# BaseBoard_2x5.net
KiCad netlist of a schematic drawn in EAGLE
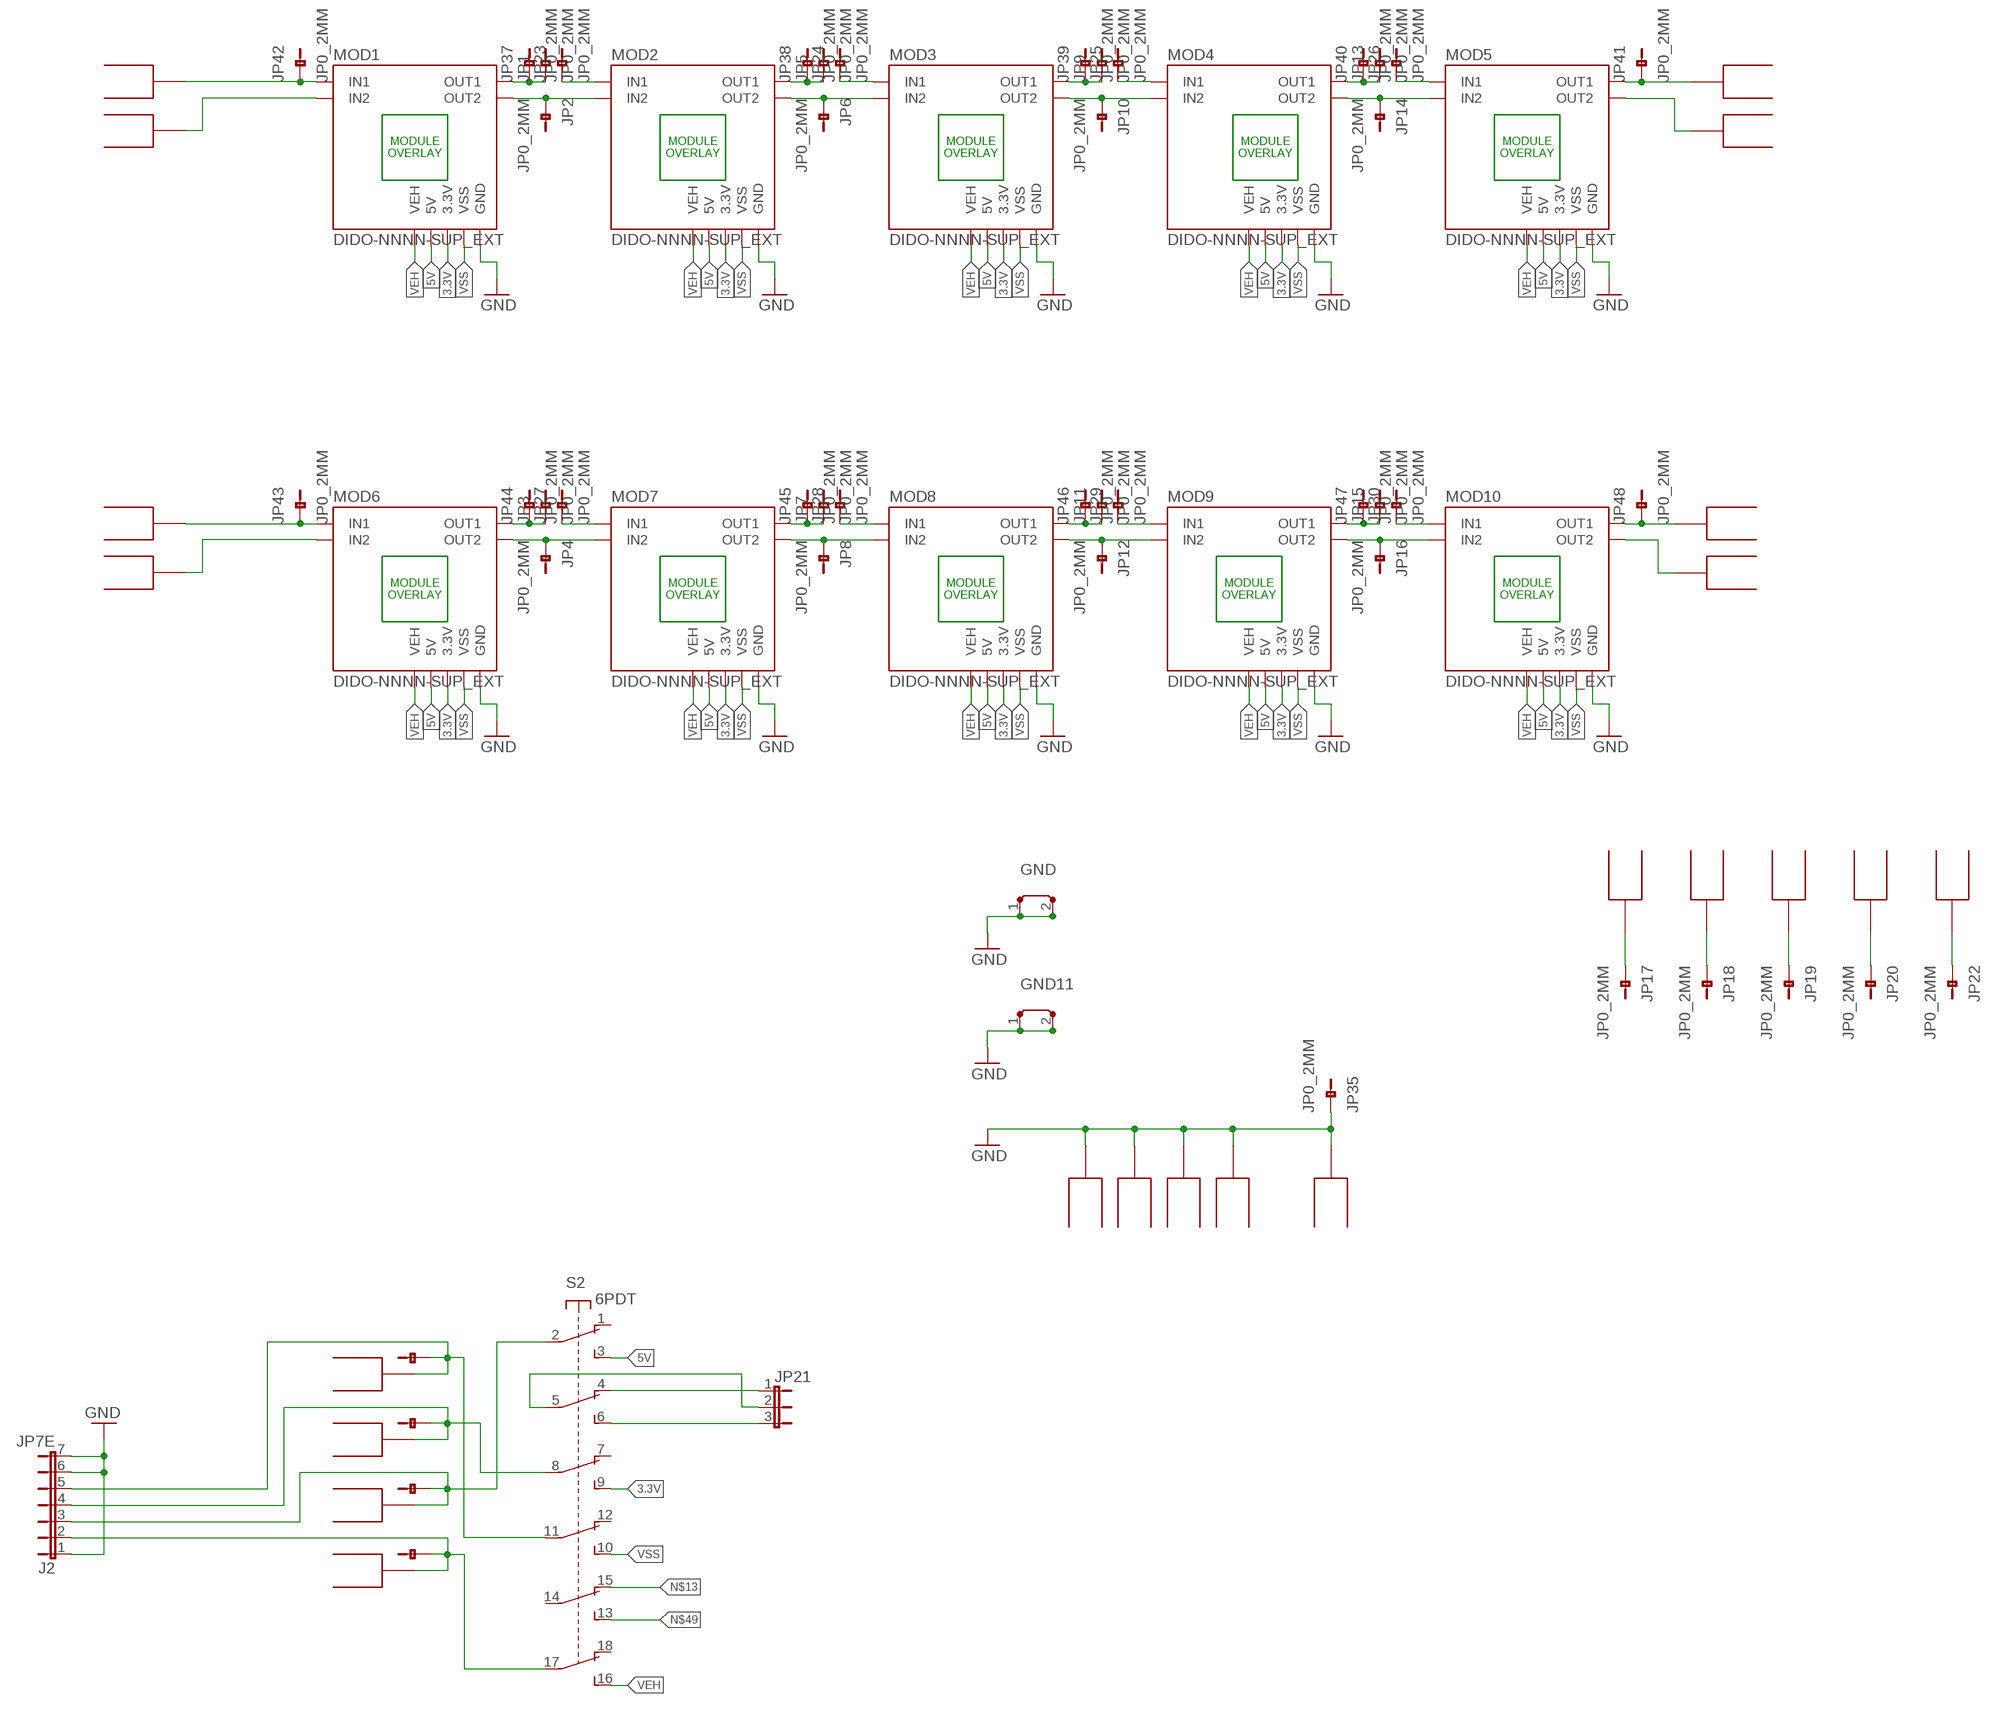
[diagram p0: schematic, sheet 1]

(export (version "E")
  (design (tool "Eeschema 10.0.6"))
  (components
    (comp (ref "GND")
      (value "TE4/2")
      (footprint "eagle-import:TE4_2")
      (libsource (lib "eagle-import") (part "TE4/2"))
    )
    (comp (ref "GND11")
      (value "TE4/2")
      (footprint "eagle-import:TE4_2")
      (libsource (lib "eagle-import") (part "TE4/2"))
    )
    (comp (ref "J2")
      (value "JP7E")
      (footprint "eagle-import:JP7")
      (libsource (lib "eagle-import") (part "JP7E"))
    )
    (comp (ref "JP1")
      (value "JP0_2MM")
      (footprint "eagle-import:JP0-2MM")
      (libsource (lib "eagle-import") (part "JP0_2MM"))
    )
    (comp (ref "JP2")
      (value "JP0_2MM")
      (footprint "eagle-import:JP0-2MM")
      (libsource (lib "eagle-import") (part "JP0_2MM"))
    )
    (comp (ref "JP3")
      (value "JP0_2MM")
      (footprint "eagle-import:JP0-2MM")
      (libsource (lib "eagle-import") (part "JP0_2MM"))
    )
    (comp (ref "JP4")
      (value "JP0_2MM")
      (footprint "eagle-import:JP0-2MM")
      (libsource (lib "eagle-import") (part "JP0_2MM"))
    )
    (comp (ref "JP5")
      (value "JP0_2MM")
      (footprint "eagle-import:JP0-2MM")
      (libsource (lib "eagle-import") (part "JP0_2MM"))
    )
    (comp (ref "JP6")
      (value "JP0_2MM")
      (footprint "eagle-import:JP0-2MM")
      (libsource (lib "eagle-import") (part "JP0_2MM"))
    )
    (comp (ref "JP7")
      (value "JP0_2MM")
      (footprint "eagle-import:JP0-2MM")
      (libsource (lib "eagle-import") (part "JP0_2MM"))
    )
    (comp (ref "JP8")
      (value "JP0_2MM")
      (footprint "eagle-import:JP0-2MM")
      (libsource (lib "eagle-import") (part "JP0_2MM"))
    )
    (comp (ref "JP9")
      (value "JP0_2MM")
      (footprint "eagle-import:JP0-2MM")
      (libsource (lib "eagle-import") (part "JP0_2MM"))
    )
    (comp (ref "JP10")
      (value "JP0_2MM")
      (footprint "eagle-import:JP0-2MM")
      (libsource (lib "eagle-import") (part "JP0_2MM"))
    )
    (comp (ref "JP11")
      (value "JP0_2MM")
      (footprint "eagle-import:JP0-2MM")
      (libsource (lib "eagle-import") (part "JP0_2MM"))
    )
    (comp (ref "JP12")
      (value "JP0_2MM")
      (footprint "eagle-import:JP0-2MM")
      (libsource (lib "eagle-import") (part "JP0_2MM"))
    )
    (comp (ref "JP13")
      (value "JP0_2MM")
      (footprint "eagle-import:JP0-2MM")
      (libsource (lib "eagle-import") (part "JP0_2MM"))
    )
    (comp (ref "JP14")
      (value "JP0_2MM")
      (footprint "eagle-import:JP0-2MM")
      (libsource (lib "eagle-import") (part "JP0_2MM"))
    )
    (comp (ref "JP15")
      (value "JP0_2MM")
      (footprint "eagle-import:JP0-2MM")
      (libsource (lib "eagle-import") (part "JP0_2MM"))
    )
    (comp (ref "JP16")
      (value "JP0_2MM")
      (footprint "eagle-import:JP0-2MM")
      (libsource (lib "eagle-import") (part "JP0_2MM"))
    )
    (comp (ref "JP17")
      (value "JP0_2MM")
      (footprint "eagle-import:JP0-2MM")
      (libsource (lib "eagle-import") (part "JP0_2MM"))
    )
    (comp (ref "JP18")
      (value "JP0_2MM")
      (footprint "eagle-import:JP0-2MM")
      (libsource (lib "eagle-import") (part "JP0_2MM"))
    )
    (comp (ref "JP19")
      (value "JP0_2MM")
      (footprint "eagle-import:JP0-2MM")
      (libsource (lib "eagle-import") (part "JP0_2MM"))
    )
    (comp (ref "JP20")
      (value "JP0_2MM")
      (footprint "eagle-import:JP0-2MM")
      (libsource (lib "eagle-import") (part "JP0_2MM"))
    )
    (comp (ref "JP21")
      (value "JP2E")
      (footprint "eagle-import:JP2")
      (libsource (lib "eagle-import") (part "JP2E"))
    )
    (comp (ref "JP22")
      (value "JP0_2MM")
      (footprint "eagle-import:JP0-2MM")
      (libsource (lib "eagle-import") (part "JP0_2MM"))
    )
    (comp (ref "JP23")
      (value "JP0_2MM")
      (footprint "eagle-import:JP0-2MM")
      (libsource (lib "eagle-import") (part "JP0_2MM"))
    )
    (comp (ref "JP24")
      (value "JP0_2MM")
      (footprint "eagle-import:JP0-2MM")
      (libsource (lib "eagle-import") (part "JP0_2MM"))
    )
    (comp (ref "JP25")
      (value "JP0_2MM")
      (footprint "eagle-import:JP0-2MM")
      (libsource (lib "eagle-import") (part "JP0_2MM"))
    )
    (comp (ref "JP26")
      (value "JP0_2MM")
      (footprint "eagle-import:JP0-2MM")
      (libsource (lib "eagle-import") (part "JP0_2MM"))
    )
    (comp (ref "JP27")
      (value "JP0_2MM")
      (footprint "eagle-import:JP0-2MM")
      (libsource (lib "eagle-import") (part "JP0_2MM"))
    )
    (comp (ref "JP28")
      (value "JP0_2MM")
      (footprint "eagle-import:JP0-2MM")
      (libsource (lib "eagle-import") (part "JP0_2MM"))
    )
    (comp (ref "JP29")
      (value "JP0_2MM")
      (footprint "eagle-import:JP0-2MM")
      (libsource (lib "eagle-import") (part "JP0_2MM"))
    )
    (comp (ref "JP30")
      (value "JP0_2MM")
      (footprint "eagle-import:JP0-2MM")
      (libsource (lib "eagle-import") (part "JP0_2MM"))
    )
    (comp (ref "JP35")
      (value "JP0_2MM")
      (footprint "eagle-import:JP0-2MM")
      (libsource (lib "eagle-import") (part "JP0_2MM"))
    )
    (comp (ref "JP37")
      (value "JP0_2MM")
      (footprint "eagle-import:JP0-2MM")
      (libsource (lib "eagle-import") (part "JP0_2MM"))
    )
    (comp (ref "JP38")
      (value "JP0_2MM")
      (footprint "eagle-import:JP0-2MM")
      (libsource (lib "eagle-import") (part "JP0_2MM"))
    )
    (comp (ref "JP39")
      (value "JP0_2MM")
      (footprint "eagle-import:JP0-2MM")
      (libsource (lib "eagle-import") (part "JP0_2MM"))
    )
    (comp (ref "JP40")
      (value "JP0_2MM")
      (footprint "eagle-import:JP0-2MM")
      (libsource (lib "eagle-import") (part "JP0_2MM"))
    )
    (comp (ref "JP41")
      (value "JP0_2MM")
      (footprint "eagle-import:JP0-2MM")
      (libsource (lib "eagle-import") (part "JP0_2MM"))
    )
    (comp (ref "JP42")
      (value "JP0_2MM")
      (footprint "eagle-import:JP0-2MM")
      (libsource (lib "eagle-import") (part "JP0_2MM"))
    )
    (comp (ref "JP43")
      (value "JP0_2MM")
      (footprint "eagle-import:JP0-2MM")
      (libsource (lib "eagle-import") (part "JP0_2MM"))
    )
    (comp (ref "JP44")
      (value "JP0_2MM")
      (footprint "eagle-import:JP0-2MM")
      (libsource (lib "eagle-import") (part "JP0_2MM"))
    )
    (comp (ref "JP45")
      (value "JP0_2MM")
      (footprint "eagle-import:JP0-2MM")
      (libsource (lib "eagle-import") (part "JP0_2MM"))
    )
    (comp (ref "JP46")
      (value "JP0_2MM")
      (footprint "eagle-import:JP0-2MM")
      (libsource (lib "eagle-import") (part "JP0_2MM"))
    )
    (comp (ref "JP47")
      (value "JP0_2MM")
      (footprint "eagle-import:JP0-2MM")
      (libsource (lib "eagle-import") (part "JP0_2MM"))
    )
    (comp (ref "JP48")
      (value "JP0_2MM")
      (footprint "eagle-import:JP0-2MM")
      (libsource (lib "eagle-import") (part "JP0_2MM"))
    )
    (comp (ref "JP53")
      (value "JP0_2MM")
      (footprint "eagle-import:JP0-2MM")
      (libsource (lib "eagle-import") (part "JP0_2MM"))
    )
    (comp (ref "JP54")
      (value "JP0_2MM")
      (footprint "eagle-import:JP0-2MM")
      (libsource (lib "eagle-import") (part "JP0_2MM"))
    )
    (comp (ref "JP55")
      (value "JP0_2MM")
      (footprint "eagle-import:JP0-2MM")
      (libsource (lib "eagle-import") (part "JP0_2MM"))
    )
    (comp (ref "JP56")
      (value "JP0_2MM")
      (footprint "eagle-import:JP0-2MM")
      (libsource (lib "eagle-import") (part "JP0_2MM"))
    )
    (comp (ref "MOD1")
      (value "DIDO-NNNN-SUP_EXT")
      (footprint "eagle-import:DIDO-NNNN-SUP_EXT")
      (libsource (lib "eagle-import") (part "DIDO-NNNN-SUP_EXT"))
    )
    (comp (ref "MOD2")
      (value "DIDO-NNNN-SUP_EXT")
      (footprint "eagle-import:DIDO-NNNN-SUP_EXT")
      (libsource (lib "eagle-import") (part "DIDO-NNNN-SUP_EXT"))
    )
    (comp (ref "MOD3")
      (value "DIDO-NNNN-SUP_EXT")
      (footprint "eagle-import:DIDO-NNNN-SUP_EXT")
      (libsource (lib "eagle-import") (part "DIDO-NNNN-SUP_EXT"))
    )
    (comp (ref "MOD4")
      (value "DIDO-NNNN-SUP_EXT")
      (footprint "eagle-import:DIDO-NNNN-SUP_EXT")
      (libsource (lib "eagle-import") (part "DIDO-NNNN-SUP_EXT"))
    )
    (comp (ref "MOD5")
      (value "DIDO-NNNN-SUP_EXT")
      (footprint "eagle-import:DIDO-NNNN-SUP_EXT")
      (libsource (lib "eagle-import") (part "DIDO-NNNN-SUP_EXT"))
    )
    (comp (ref "MOD6")
      (value "DIDO-NNNN-SUP_EXT")
      (footprint "eagle-import:DIDO-NNNN-SUP_EXT")
      (libsource (lib "eagle-import") (part "DIDO-NNNN-SUP_EXT"))
    )
    (comp (ref "MOD7")
      (value "DIDO-NNNN-SUP_EXT")
      (footprint "eagle-import:DIDO-NNNN-SUP_EXT")
      (libsource (lib "eagle-import") (part "DIDO-NNNN-SUP_EXT"))
    )
    (comp (ref "MOD8")
      (value "DIDO-NNNN-SUP_EXT")
      (footprint "eagle-import:DIDO-NNNN-SUP_EXT")
      (libsource (lib "eagle-import") (part "DIDO-NNNN-SUP_EXT"))
    )
    (comp (ref "MOD9")
      (value "DIDO-NNNN-SUP_EXT")
      (footprint "eagle-import:DIDO-NNNN-SUP_EXT")
      (libsource (lib "eagle-import") (part "DIDO-NNNN-SUP_EXT"))
    )
    (comp (ref "MOD10")
      (value "DIDO-NNNN-SUP_EXT")
      (footprint "eagle-import:DIDO-NNNN-SUP_EXT")
      (libsource (lib "eagle-import") (part "DIDO-NNNN-SUP_EXT"))
    )
    (comp (ref "MODULE1")
      (value "MODULE_OVERLAY")
      (footprint "eagle-import:MODULE_OVERLAY")
      (libsource (lib "eagle-import") (part "MODULE_OVERLAY"))
    )
    (comp (ref "MODULE2")
      (value "MODULE_OVERLAY")
      (footprint "eagle-import:MODULE_OVERLAY")
      (libsource (lib "eagle-import") (part "MODULE_OVERLAY"))
    )
    (comp (ref "MODULE3")
      (value "MODULE_OVERLAY")
      (footprint "eagle-import:MODULE_OVERLAY")
      (libsource (lib "eagle-import") (part "MODULE_OVERLAY"))
    )
    (comp (ref "MODULE4")
      (value "MODULE_OVERLAY")
      (footprint "eagle-import:MODULE_OVERLAY")
      (libsource (lib "eagle-import") (part "MODULE_OVERLAY"))
    )
    (comp (ref "MODULE5")
      (value "MODULE_OVERLAY")
      (footprint "eagle-import:MODULE_OVERLAY")
      (libsource (lib "eagle-import") (part "MODULE_OVERLAY"))
    )
    (comp (ref "MODULE6")
      (value "MODULE_OVERLAY")
      (footprint "eagle-import:MODULE_OVERLAY")
      (libsource (lib "eagle-import") (part "MODULE_OVERLAY"))
    )
    (comp (ref "MODULE7")
      (value "MODULE_OVERLAY")
      (footprint "eagle-import:MODULE_OVERLAY")
      (libsource (lib "eagle-import") (part "MODULE_OVERLAY"))
    )
    (comp (ref "MODULE8")
      (value "MODULE_OVERLAY")
      (footprint "eagle-import:MODULE_OVERLAY")
      (libsource (lib "eagle-import") (part "MODULE_OVERLAY"))
    )
    (comp (ref "MODULE9")
      (value "MODULE_OVERLAY")
      (footprint "eagle-import:MODULE_OVERLAY")
      (libsource (lib "eagle-import") (part "MODULE_OVERLAY"))
    )
    (comp (ref "MODULE10")
      (value "MODULE_OVERLAY")
      (footprint "eagle-import:MODULE_OVERLAY")
      (libsource (lib "eagle-import") (part "MODULE_OVERLAY"))
    )
    (comp (ref "P1")
      (value "BANANA-PLUGROUND")
      (footprint "eagle-import:6MM-PAD-ROUND")
      (libsource (lib "eagle-import") (part "BANANA-PLUGROUND"))
    )
    (comp (ref "P2")
      (value "BANANA-PLUGROUND")
      (footprint "eagle-import:6MM-PAD-ROUND")
      (libsource (lib "eagle-import") (part "BANANA-PLUGROUND"))
    )
    (comp (ref "P3")
      (value "BANANA-PLUGROUND")
      (footprint "eagle-import:6MM-PAD-ROUND")
      (libsource (lib "eagle-import") (part "BANANA-PLUGROUND"))
    )
    (comp (ref "P4")
      (value "BANANA-PLUGROUND")
      (footprint "eagle-import:6MM-PAD-ROUND")
      (libsource (lib "eagle-import") (part "BANANA-PLUGROUND"))
    )
    (comp (ref "P5")
      (value "BANANA-PLUGROUND")
      (footprint "eagle-import:6MM-PAD-ROUND")
      (libsource (lib "eagle-import") (part "BANANA-PLUGROUND"))
    )
    (comp (ref "P6")
      (value "BANANA-PLUGROUND")
      (footprint "eagle-import:6MM-PAD-ROUND")
      (libsource (lib "eagle-import") (part "BANANA-PLUGROUND"))
    )
    (comp (ref "P10")
      (value "BANANA-PLUGROUND")
      (footprint "eagle-import:6MM-PAD-ROUND")
      (libsource (lib "eagle-import") (part "BANANA-PLUGROUND"))
    )
    (comp (ref "P11")
      (value "BANANA-PLUGROUND")
      (footprint "eagle-import:6MM-PAD-ROUND")
      (libsource (lib "eagle-import") (part "BANANA-PLUGROUND"))
    )
    (comp (ref "P12")
      (value "BANANA-PLUGROUND")
      (footprint "eagle-import:6MM-PAD-ROUND")
      (libsource (lib "eagle-import") (part "BANANA-PLUGROUND"))
    )
    (comp (ref "P13")
      (value "BANANA-PLUGROUND")
      (footprint "eagle-import:6MM-PAD-ROUND")
      (libsource (lib "eagle-import") (part "BANANA-PLUGROUND"))
    )
    (comp (ref "P14")
      (value "BANANA-PLUGROUND")
      (footprint "eagle-import:6MM-PAD-ROUND")
      (libsource (lib "eagle-import") (part "BANANA-PLUGROUND"))
    )
    (comp (ref "P15")
      (value "BANANA-PLUGROUND")
      (footprint "eagle-import:6MM-PAD-ROUND")
      (libsource (lib "eagle-import") (part "BANANA-PLUGROUND"))
    )
    (comp (ref "P16")
      (value "BANANA-PLUGROUND")
      (footprint "eagle-import:6MM-PAD-ROUND")
      (libsource (lib "eagle-import") (part "BANANA-PLUGROUND"))
    )
    (comp (ref "P18")
      (value "BANANA-PLUGROUND")
      (footprint "eagle-import:6MM-PAD-ROUND")
      (libsource (lib "eagle-import") (part "BANANA-PLUGROUND"))
    )
    (comp (ref "P19")
      (value "BANANA-PLUGROUND")
      (footprint "eagle-import:6MM-PAD-ROUND")
      (libsource (lib "eagle-import") (part "BANANA-PLUGROUND"))
    )
    (comp (ref "P20")
      (value "BANANA-PLUGROUND")
      (footprint "eagle-import:6MM-PAD-ROUND")
      (libsource (lib "eagle-import") (part "BANANA-PLUGROUND"))
    )
    (comp (ref "P21")
      (value "BANANA-PLUGROUND")
      (footprint "eagle-import:6MM-PAD-ROUND")
      (libsource (lib "eagle-import") (part "BANANA-PLUGROUND"))
    )
    (comp (ref "P22")
      (value "BANANA-PLUGROUND")
      (footprint "eagle-import:6MM-PAD-ROUND")
      (libsource (lib "eagle-import") (part "BANANA-PLUGROUND"))
    )
    (comp (ref "P23")
      (value "BANANA-PLUGROUND")
      (footprint "eagle-import:6MM-PAD-ROUND")
      (libsource (lib "eagle-import") (part "BANANA-PLUGROUND"))
    )
    (comp (ref "P24")
      (value "BANANA-PLUGROUND")
      (footprint "eagle-import:6MM-PAD-ROUND")
      (libsource (lib "eagle-import") (part "BANANA-PLUGROUND"))
    )
    (comp (ref "P27")
      (value "BANANA-PLUGROUND")
      (footprint "eagle-import:6MM-PAD-ROUND")
      (libsource (lib "eagle-import") (part "BANANA-PLUGROUND"))
    )
    (comp (ref "P28")
      (value "BANANA-PLUGROUND")
      (footprint "eagle-import:6MM-PAD-ROUND")
      (libsource (lib "eagle-import") (part "BANANA-PLUGROUND"))
    )
    (comp (ref "S2")
      (value "6PDT")
      (footprint "eagle-import:DIL18")
      (libsource (lib "eagle-import") (part "6PDT"))
    )
  )
  (nets
    (net (code "1") (name "3.3V") (class "Default")
      (node (ref "MOD1") (pin "3.3V") (pinfunction "3.3V_3.3V") (pintype "power_in"))
      (node (ref "MOD10") (pin "3.3V") (pinfunction "3.3V_3.3V") (pintype "power_in"))
      (node (ref "MOD2") (pin "3.3V") (pinfunction "3.3V_3.3V") (pintype "power_in"))
      (node (ref "MOD3") (pin "3.3V") (pinfunction "3.3V_3.3V") (pintype "power_in"))
      (node (ref "MOD4") (pin "3.3V") (pinfunction "3.3V_3.3V") (pintype "power_in"))
      (node (ref "MOD5") (pin "3.3V") (pinfunction "3.3V_3.3V") (pintype "power_in"))
      (node (ref "MOD6") (pin "3.3V") (pinfunction "3.3V_3.3V") (pintype "power_in"))
      (node (ref "MOD7") (pin "3.3V") (pinfunction "3.3V_3.3V") (pintype "power_in"))
      (node (ref "MOD8") (pin "3.3V") (pinfunction "3.3V_3.3V") (pintype "power_in"))
      (node (ref "MOD9") (pin "3.3V") (pinfunction "3.3V_3.3V") (pintype "power_in"))
      (node (ref "S2") (pin "9") (pinfunction "S3_9") (pintype "passive"))
    )
    (net (code "2") (name "5V") (class "Default")
      (node (ref "MOD1") (pin "5V") (pinfunction "5V_5V") (pintype "power_in"))
      (node (ref "MOD10") (pin "5V") (pinfunction "5V_5V") (pintype "power_in"))
      (node (ref "MOD2") (pin "5V") (pinfunction "5V_5V") (pintype "power_in"))
      (node (ref "MOD3") (pin "5V") (pinfunction "5V_5V") (pintype "power_in"))
      (node (ref "MOD4") (pin "5V") (pinfunction "5V_5V") (pintype "power_in"))
      (node (ref "MOD5") (pin "5V") (pinfunction "5V_5V") (pintype "power_in"))
      (node (ref "MOD6") (pin "5V") (pinfunction "5V_5V") (pintype "power_in"))
      (node (ref "MOD7") (pin "5V") (pinfunction "5V_5V") (pintype "power_in"))
      (node (ref "MOD8") (pin "5V") (pinfunction "5V_5V") (pintype "power_in"))
      (node (ref "MOD9") (pin "5V") (pinfunction "5V_5V") (pintype "power_in"))
      (node (ref "S2") (pin "3") (pinfunction "S1_3") (pintype "passive"))
    )
    (net (code "3") (name "GND") (class "Default")
      (node (ref "GND") (pin "1") (pinfunction "P_1") (pintype "passive"))
      (node (ref "GND") (pin "2") (pinfunction "P_2") (pintype "passive"))
      (node (ref "GND11") (pin "1") (pinfunction "P_1") (pintype "passive"))
      (node (ref "GND11") (pin "2") (pinfunction "P_2") (pintype "passive"))
      (node (ref "J2") (pin "1") (pinfunction "1_1") (pintype "passive"))
      (node (ref "J2") (pin "6") (pinfunction "6_6") (pintype "passive"))
      (node (ref "J2") (pin "7") (pinfunction "7_7") (pintype "passive"))
      (node (ref "JP35") (pin "1") (pinfunction "1_1") (pintype "passive"))
      (node (ref "MOD1") (pin "GND1") (pinfunction "GND_GND1") (pintype "power_in"))
      (node (ref "MOD1") (pin "GND2") (pinfunction "GND_GND2") (pintype "power_in"))
      (node (ref "MOD1") (pin "GND3") (pinfunction "GND_GND3") (pintype "power_in"))
      (node (ref "MOD1") (pin "GND4") (pinfunction "GND_GND4") (pintype "power_in"))
      (node (ref "MOD10") (pin "GND1") (pinfunction "GND_GND1") (pintype "power_in"))
      (node (ref "MOD10") (pin "GND2") (pinfunction "GND_GND2") (pintype "power_in"))
      (node (ref "MOD10") (pin "GND3") (pinfunction "GND_GND3") (pintype "power_in"))
      (node (ref "MOD10") (pin "GND4") (pinfunction "GND_GND4") (pintype "power_in"))
      (node (ref "MOD2") (pin "GND1") (pinfunction "GND_GND1") (pintype "power_in"))
      (node (ref "MOD2") (pin "GND2") (pinfunction "GND_GND2") (pintype "power_in"))
      (node (ref "MOD2") (pin "GND3") (pinfunction "GND_GND3") (pintype "power_in"))
      (node (ref "MOD2") (pin "GND4") (pinfunction "GND_GND4") (pintype "power_in"))
      (node (ref "MOD3") (pin "GND1") (pinfunction "GND_GND1") (pintype "power_in"))
      (node (ref "MOD3") (pin "GND2") (pinfunction "GND_GND2") (pintype "power_in"))
      (node (ref "MOD3") (pin "GND3") (pinfunction "GND_GND3") (pintype "power_in"))
      (node (ref "MOD3") (pin "GND4") (pinfunction "GND_GND4") (pintype "power_in"))
      (node (ref "MOD4") (pin "GND1") (pinfunction "GND_GND1") (pintype "power_in"))
      (node (ref "MOD4") (pin "GND2") (pinfunction "GND_GND2") (pintype "power_in"))
      (node (ref "MOD4") (pin "GND3") (pinfunction "GND_GND3") (pintype "power_in"))
      (node (ref "MOD4") (pin "GND4") (pinfunction "GND_GND4") (pintype "power_in"))
      (node (ref "MOD5") (pin "GND1") (pinfunction "GND_GND1") (pintype "power_in"))
      (node (ref "MOD5") (pin "GND2") (pinfunction "GND_GND2") (pintype "power_in"))
      (node (ref "MOD5") (pin "GND3") (pinfunction "GND_GND3") (pintype "power_in"))
      (node (ref "MOD5") (pin "GND4") (pinfunction "GND_GND4") (pintype "power_in"))
      (node (ref "MOD6") (pin "GND1") (pinfunction "GND_GND1") (pintype "power_in"))
      (node (ref "MOD6") (pin "GND2") (pinfunction "GND_GND2") (pintype "power_in"))
      (node (ref "MOD6") (pin "GND3") (pinfunction "GND_GND3") (pintype "power_in"))
      (node (ref "MOD6") (pin "GND4") (pinfunction "GND_GND4") (pintype "power_in"))
      (node (ref "MOD7") (pin "GND1") (pinfunction "GND_GND1") (pintype "power_in"))
      (node (ref "MOD7") (pin "GND2") (pinfunction "GND_GND2") (pintype "power_in"))
      (node (ref "MOD7") (pin "GND3") (pinfunction "GND_GND3") (pintype "power_in"))
      (node (ref "MOD7") (pin "GND4") (pinfunction "GND_GND4") (pintype "power_in"))
      (node (ref "MOD8") (pin "GND1") (pinfunction "GND_GND1") (pintype "power_in"))
      (node (ref "MOD8") (pin "GND2") (pinfunction "GND_GND2") (pintype "power_in"))
      (node (ref "MOD8") (pin "GND3") (pinfunction "GND_GND3") (pintype "power_in"))
      (node (ref "MOD8") (pin "GND4") (pinfunction "GND_GND4") (pintype "power_in"))
      (node (ref "MOD9") (pin "GND1") (pinfunction "GND_GND1") (pintype "power_in"))
      (node (ref "MOD9") (pin "GND2") (pinfunction "GND_GND2") (pintype "power_in"))
      (node (ref "MOD9") (pin "GND3") (pinfunction "GND_GND3") (pintype "power_in"))
      (node (ref "MOD9") (pin "GND4") (pinfunction "GND_GND4") (pintype "power_in"))
      (node (ref "P14") (pin "1") (pinfunction "P$1_1") (pintype "bidirectional"))
      (node (ref "P15") (pin "1") (pinfunction "P$1_1") (pintype "bidirectional"))
      (node (ref "P16") (pin "1") (pinfunction "P$1_1") (pintype "bidirectional"))
      (node (ref "P18") (pin "1") (pinfunction "P$1_1") (pintype "bidirectional"))
      (node (ref "P5") (pin "1") (pinfunction "P$1_1") (pintype "bidirectional"))
    )
    (net (code "4") (name "N$13") (class "Default")
      (node (ref "J2") (pin "3") (pinfunction "3_3") (pintype "passive"))
      (node (ref "JP54") (pin "1") (pinfunction "1_1") (pintype "passive"))
      (node (ref "P27") (pin "1") (pinfunction "P$1_1") (pintype "bidirectional"))
      (node (ref "S2") (pin "15") (pinfunction "O5_15") (pintype "passive"))
      (node (ref "S2") (pin "2") (pinfunction "P1_2") (pintype "passive"))
    )
    (net (code "5") (name "N$49") (class "Default")
      (node (ref "J2") (pin "4") (pinfunction "4_4") (pintype "passive"))
      (node (ref "JP55") (pin "1") (pinfunction "1_1") (pintype "passive"))
      (node (ref "P24") (pin "1") (pinfunction "P$1_1") (pintype "bidirectional"))
      (node (ref "S2") (pin "13") (pinfunction "S5_13") (pintype "passive"))
      (node (ref "S2") (pin "8") (pinfunction "P3_8") (pintype "passive"))
    )
    (net (code "6") (name "Net-(JP1-Pad1)") (class "Default")
      (node (ref "JP1") (pin "1") (pinfunction "1_1") (pintype "passive"))
      (node (ref "JP37") (pin "1") (pinfunction "1_1") (pintype "passive"))
      (node (ref "MOD1") (pin "OUT1") (pinfunction "OUT1_OUT1") (pintype "output"))
      (node (ref "MOD1") (pin "OUT2") (pinfunction "OUT1_OUT2") (pintype "output"))
      (node (ref "MOD1") (pin "OUT3") (pinfunction "OUT1_OUT3") (pintype "output"))
      (node (ref "MOD1") (pin "OUT4") (pinfunction "OUT1_OUT4") (pintype "output"))
    )
    (net (code "7") (name "Net-(JP2-Pad1)") (class "Default")
      (node (ref "JP2") (pin "1") (pinfunction "1_1") (pintype "passive"))
      (node (ref "MOD1") (pin "OUT2_1") (pinfunction "OUT2_OUT2_1") (pintype "output"))
      (node (ref "MOD1") (pin "OUT2_2") (pinfunction "OUT2_OUT2_2") (pintype "output"))
      (node (ref "MOD1") (pin "OUT2_3") (pinfunction "OUT2_OUT2_3") (pintype "output"))
      (node (ref "MOD1") (pin "OUT2_4") (pinfunction "OUT2_OUT2_4") (pintype "output"))
      (node (ref "MOD2") (pin "IN2_1") (pinfunction "IN2_IN2_1") (pintype "input"))
      (node (ref "MOD2") (pin "IN2_2") (pinfunction "IN2_IN2_2") (pintype "input"))
      (node (ref "MOD2") (pin "IN2_3") (pinfunction "IN2_IN2_3") (pintype "input"))
      (node (ref "MOD2") (pin "IN2_4") (pinfunction "IN2_IN2_4") (pintype "input"))
    )
    (net (code "8") (name "Net-(JP3-Pad1)") (class "Default")
      (node (ref "JP3") (pin "1") (pinfunction "1_1") (pintype "passive"))
      (node (ref "JP44") (pin "1") (pinfunction "1_1") (pintype "passive"))
      (node (ref "MOD6") (pin "OUT1") (pinfunction "OUT1_OUT1") (pintype "output"))
      (node (ref "MOD6") (pin "OUT2") (pinfunction "OUT1_OUT2") (pintype "output"))
      (node (ref "MOD6") (pin "OUT3") (pinfunction "OUT1_OUT3") (pintype "output"))
      (node (ref "MOD6") (pin "OUT4") (pinfunction "OUT1_OUT4") (pintype "output"))
    )
    (net (code "9") (name "Net-(JP4-Pad1)") (class "Default")
      (node (ref "JP4") (pin "1") (pinfunction "1_1") (pintype "passive"))
      (node (ref "MOD6") (pin "OUT2_1") (pinfunction "OUT2_OUT2_1") (pintype "output"))
      (node (ref "MOD6") (pin "OUT2_2") (pinfunction "OUT2_OUT2_2") (pintype "output"))
      (node (ref "MOD6") (pin "OUT2_3") (pinfunction "OUT2_OUT2_3") (pintype "output"))
      (node (ref "MOD6") (pin "OUT2_4") (pinfunction "OUT2_OUT2_4") (pintype "output"))
      (node (ref "MOD7") (pin "IN2_1") (pinfunction "IN2_IN2_1") (pintype "input"))
      (node (ref "MOD7") (pin "IN2_2") (pinfunction "IN2_IN2_2") (pintype "input"))
      (node (ref "MOD7") (pin "IN2_3") (pinfunction "IN2_IN2_3") (pintype "input"))
      (node (ref "MOD7") (pin "IN2_4") (pinfunction "IN2_IN2_4") (pintype "input"))
    )
    (net (code "10") (name "Net-(JP6-Pad1)") (class "Default")
      (node (ref "JP6") (pin "1") (pinfunction "1_1") (pintype "passive"))
      (node (ref "MOD2") (pin "OUT2_1") (pinfunction "OUT2_OUT2_1") (pintype "output"))
      (node (ref "MOD2") (pin "OUT2_2") (pinfunction "OUT2_OUT2_2") (pintype "output"))
      (node (ref "MOD2") (pin "OUT2_3") (pinfunction "OUT2_OUT2_3") (pintype "output"))
      (node (ref "MOD2") (pin "OUT2_4") (pinfunction "OUT2_OUT2_4") (pintype "output"))
      (node (ref "MOD3") (pin "IN2_1") (pinfunction "IN2_IN2_1") (pintype "input"))
      (node (ref "MOD3") (pin "IN2_2") (pinfunction "IN2_IN2_2") (pintype "input"))
      (node (ref "MOD3") (pin "IN2_3") (pinfunction "IN2_IN2_3") (pintype "input"))
      (node (ref "MOD3") (pin "IN2_4") (pinfunction "IN2_IN2_4") (pintype "input"))
    )
    (net (code "11") (name "Net-(JP8-Pad1)") (class "Default")
      (node (ref "JP8") (pin "1") (pinfunction "1_1") (pintype "passive"))
      (node (ref "MOD7") (pin "OUT2_1") (pinfunction "OUT2_OUT2_1") (pintype "output"))
      (node (ref "MOD7") (pin "OUT2_2") (pinfunction "OUT2_OUT2_2") (pintype "output"))
      (node (ref "MOD7") (pin "OUT2_3") (pinfunction "OUT2_OUT2_3") (pintype "output"))
      (node (ref "MOD7") (pin "OUT2_4") (pinfunction "OUT2_OUT2_4") (pintype "output"))
      (node (ref "MOD8") (pin "IN2_1") (pinfunction "IN2_IN2_1") (pintype "input"))
      (node (ref "MOD8") (pin "IN2_2") (pinfunction "IN2_IN2_2") (pintype "input"))
      (node (ref "MOD8") (pin "IN2_3") (pinfunction "IN2_IN2_3") (pintype "input"))
      (node (ref "MOD8") (pin "IN2_4") (pinfunction "IN2_IN2_4") (pintype "input"))
    )
    (net (code "12") (name "Net-(JP10-Pad1)") (class "Default")
      (node (ref "JP10") (pin "1") (pinfunction "1_1") (pintype "passive"))
      (node (ref "MOD3") (pin "OUT2_1") (pinfunction "OUT2_OUT2_1") (pintype "output"))
      (node (ref "MOD3") (pin "OUT2_2") (pinfunction "OUT2_OUT2_2") (pintype "output"))
      (node (ref "MOD3") (pin "OUT2_3") (pinfunction "OUT2_OUT2_3") (pintype "output"))
      (node (ref "MOD3") (pin "OUT2_4") (pinfunction "OUT2_OUT2_4") (pintype "output"))
      (node (ref "MOD4") (pin "IN2_1") (pinfunction "IN2_IN2_1") (pintype "input"))
      (node (ref "MOD4") (pin "IN2_2") (pinfunction "IN2_IN2_2") (pintype "input"))
      (node (ref "MOD4") (pin "IN2_3") (pinfunction "IN2_IN2_3") (pintype "input"))
      (node (ref "MOD4") (pin "IN2_4") (pinfunction "IN2_IN2_4") (pintype "input"))
    )
    (net (code "13") (name "Net-(JP11-Pad1)") (class "Default")
      (node (ref "JP11") (pin "1") (pinfunction "1_1") (pintype "passive"))
      (node (ref "JP46") (pin "1") (pinfunction "1_1") (pintype "passive"))
      (node (ref "MOD8") (pin "OUT1") (pinfunction "OUT1_OUT1") (pintype "output"))
      (node (ref "MOD8") (pin "OUT2") (pinfunction "OUT1_OUT2") (pintype "output"))
      (node (ref "MOD8") (pin "OUT3") (pinfunction "OUT1_OUT3") (pintype "output"))
      (node (ref "MOD8") (pin "OUT4") (pinfunction "OUT1_OUT4") (pintype "output"))
    )
    (net (code "14") (name "Net-(JP12-Pad1)") (class "Default")
      (node (ref "JP12") (pin "1") (pinfunction "1_1") (pintype "passive"))
      (node (ref "MOD8") (pin "OUT2_1") (pinfunction "OUT2_OUT2_1") (pintype "output"))
      (node (ref "MOD8") (pin "OUT2_2") (pinfunction "OUT2_OUT2_2") (pintype "output"))
      (node (ref "MOD8") (pin "OUT2_3") (pinfunction "OUT2_OUT2_3") (pintype "output"))
      (node (ref "MOD8") (pin "OUT2_4") (pinfunction "OUT2_OUT2_4") (pintype "output"))
      (node (ref "MOD9") (pin "IN2_1") (pinfunction "IN2_IN2_1") (pintype "input"))
      (node (ref "MOD9") (pin "IN2_2") (pinfunction "IN2_IN2_2") (pintype "input"))
      (node (ref "MOD9") (pin "IN2_3") (pinfunction "IN2_IN2_3") (pintype "input"))
      (node (ref "MOD9") (pin "IN2_4") (pinfunction "IN2_IN2_4") (pintype "input"))
    )
    (net (code "15") (name "Net-(JP13-Pad1)") (class "Default")
      (node (ref "JP13") (pin "1") (pinfunction "1_1") (pintype "passive"))
      (node (ref "JP40") (pin "1") (pinfunction "1_1") (pintype "passive"))
      (node (ref "MOD4") (pin "OUT1") (pinfunction "OUT1_OUT1") (pintype "output"))
      (node (ref "MOD4") (pin "OUT2") (pinfunction "OUT1_OUT2") (pintype "output"))
      (node (ref "MOD4") (pin "OUT3") (pinfunction "OUT1_OUT3") (pintype "output"))
      (node (ref "MOD4") (pin "OUT4") (pinfunction "OUT1_OUT4") (pintype "output"))
    )
    (net (code "16") (name "Net-(JP14-Pad1)") (class "Default")
      (node (ref "JP14") (pin "1") (pinfunction "1_1") (pintype "passive"))
      (node (ref "MOD4") (pin "OUT2_1") (pinfunction "OUT2_OUT2_1") (pintype "output"))
      (node (ref "MOD4") (pin "OUT2_2") (pinfunction "OUT2_OUT2_2") (pintype "output"))
      (node (ref "MOD4") (pin "OUT2_3") (pinfunction "OUT2_OUT2_3") (pintype "output"))
      (node (ref "MOD4") (pin "OUT2_4") (pinfunction "OUT2_OUT2_4") (pintype "output"))
      (node (ref "MOD5") (pin "IN2_1") (pinfunction "IN2_IN2_1") (pintype "input"))
      (node (ref "MOD5") (pin "IN2_2") (pinfunction "IN2_IN2_2") (pintype "input"))
      (node (ref "MOD5") (pin "IN2_3") (pinfunction "IN2_IN2_3") (pintype "input"))
      (node (ref "MOD5") (pin "IN2_4") (pinfunction "IN2_IN2_4") (pintype "input"))
    )
    (net (code "17") (name "Net-(JP15-Pad1)") (class "Default")
      (node (ref "JP15") (pin "1") (pinfunction "1_1") (pintype "passive"))
      (node (ref "JP47") (pin "1") (pinfunction "1_1") (pintype "passive"))
      (node (ref "MOD9") (pin "OUT1") (pinfunction "OUT1_OUT1") (pintype "output"))
      (node (ref "MOD9") (pin "OUT2") (pinfunction "OUT1_OUT2") (pintype "output"))
      (node (ref "MOD9") (pin "OUT3") (pinfunction "OUT1_OUT3") (pintype "output"))
      (node (ref "MOD9") (pin "OUT4") (pinfunction "OUT1_OUT4") (pintype "output"))
    )
    (net (code "18") (name "Net-(JP16-Pad1)") (class "Default")
      (node (ref "JP16") (pin "1") (pinfunction "1_1") (pintype "passive"))
      (node (ref "MOD10") (pin "IN2_1") (pinfunction "IN2_IN2_1") (pintype "input"))
      (node (ref "MOD10") (pin "IN2_2") (pinfunction "IN2_IN2_2") (pintype "input"))
      (node (ref "MOD10") (pin "IN2_3") (pinfunction "IN2_IN2_3") (pintype "input"))
      (node (ref "MOD10") (pin "IN2_4") (pinfunction "IN2_IN2_4") (pintype "input"))
      (node (ref "MOD9") (pin "OUT2_1") (pinfunction "OUT2_OUT2_1") (pintype "output"))
      (node (ref "MOD9") (pin "OUT2_2") (pinfunction "OUT2_OUT2_2") (pintype "output"))
      (node (ref "MOD9") (pin "OUT2_3") (pinfunction "OUT2_OUT2_3") (pintype "output"))
      (node (ref "MOD9") (pin "OUT2_4") (pinfunction "OUT2_OUT2_4") (pintype "output"))
    )
    (net (code "19") (name "Net-(JP23-Pad1)") (class "Default")
      (node (ref "JP23") (pin "1") (pinfunction "1_1") (pintype "passive"))
      (node (ref "MOD2") (pin "IN1") (pinfunction "IN1_IN1") (pintype "input"))
      (node (ref "MOD2") (pin "IN2") (pinfunction "IN1_IN2") (pintype "input"))
      (node (ref "MOD2") (pin "IN3") (pinfunction "IN1_IN3") (pintype "input"))
      (node (ref "MOD2") (pin "IN4") (pinfunction "IN1_IN4") (pintype "input"))
    )
    (net (code "20") (name "Net-(JP24-Pad1)") (class "Default")
      (node (ref "JP24") (pin "1") (pinfunction "1_1") (pintype "passive"))
      (node (ref "MOD3") (pin "IN1") (pinfunction "IN1_IN1") (pintype "input"))
      (node (ref "MOD3") (pin "IN2") (pinfunction "IN1_IN2") (pintype "input"))
      (node (ref "MOD3") (pin "IN3") (pinfunction "IN1_IN3") (pintype "input"))
      (node (ref "MOD3") (pin "IN4") (pinfunction "IN1_IN4") (pintype "input"))
    )
    (net (code "21") (name "Net-(JP25-Pad1)") (class "Default")
      (node (ref "JP25") (pin "1") (pinfunction "1_1") (pintype "passive"))
      (node (ref "MOD4") (pin "IN1") (pinfunction "IN1_IN1") (pintype "input"))
      (node (ref "MOD4") (pin "IN2") (pinfunction "IN1_IN2") (pintype "input"))
      (node (ref "MOD4") (pin "IN3") (pinfunction "IN1_IN3") (pintype "input"))
      (node (ref "MOD4") (pin "IN4") (pinfunction "IN1_IN4") (pintype "input"))
    )
    (net (code "22") (name "Net-(JP26-Pad1)") (class "Default")
      (node (ref "JP26") (pin "1") (pinfunction "1_1") (pintype "passive"))
      (node (ref "MOD5") (pin "IN1") (pinfunction "IN1_IN1") (pintype "input"))
      (node (ref "MOD5") (pin "IN2") (pinfunction "IN1_IN2") (pintype "input"))
      (node (ref "MOD5") (pin "IN3") (pinfunction "IN1_IN3") (pintype "input"))
      (node (ref "MOD5") (pin "IN4") (pinfunction "IN1_IN4") (pintype "input"))
    )
    (net (code "23") (name "Net-(JP27-Pad1)") (class "Default")
      (node (ref "JP27") (pin "1") (pinfunction "1_1") (pintype "passive"))
      (node (ref "MOD7") (pin "IN1") (pinfunction "IN1_IN1") (pintype "input"))
      (node (ref "MOD7") (pin "IN2") (pinfunction "IN1_IN2") (pintype "input"))
      (node (ref "MOD7") (pin "IN3") (pinfunction "IN1_IN3") (pintype "input"))
      (node (ref "MOD7") (pin "IN4") (pinfunction "IN1_IN4") (pintype "input"))
    )
    (net (code "24") (name "Net-(JP28-Pad1)") (class "Default")
      (node (ref "JP28") (pin "1") (pinfunction "1_1") (pintype "passive"))
      (node (ref "MOD8") (pin "IN1") (pinfunction "IN1_IN1") (pintype "input"))
      (node (ref "MOD8") (pin "IN2") (pinfunction "IN1_IN2") (pintype "input"))
      (node (ref "MOD8") (pin "IN3") (pinfunction "IN1_IN3") (pintype "input"))
      (node (ref "MOD8") (pin "IN4") (pinfunction "IN1_IN4") (pintype "input"))
    )
    (net (code "25") (name "Net-(JP29-Pad1)") (class "Default")
      (node (ref "JP29") (pin "1") (pinfunction "1_1") (pintype "passive"))
      (node (ref "MOD9") (pin "IN1") (pinfunction "IN1_IN1") (pintype "input"))
      (node (ref "MOD9") (pin "IN2") (pinfunction "IN1_IN2") (pintype "input"))
      (node (ref "MOD9") (pin "IN3") (pinfunction "IN1_IN3") (pintype "input"))
      (node (ref "MOD9") (pin "IN4") (pinfunction "IN1_IN4") (pintype "input"))
    )
    (net (code "26") (name "Net-(JP30-Pad1)") (class "Default")
      (node (ref "JP30") (pin "1") (pinfunction "1_1") (pintype "passive"))
      (node (ref "MOD10") (pin "IN1") (pinfunction "IN1_IN1") (pintype "input"))
      (node (ref "MOD10") (pin "IN2") (pinfunction "IN1_IN2") (pintype "input"))
      (node (ref "MOD10") (pin "IN3") (pinfunction "IN1_IN3") (pintype "input"))
      (node (ref "MOD10") (pin "IN4") (pinfunction "IN1_IN4") (pintype "input"))
    )
    (net (code "27") (name "Net-(JP38-Pad1)") (class "Default")
      (node (ref "JP38") (pin "1") (pinfunction "1_1") (pintype "passive"))
      (node (ref "JP5") (pin "1") (pinfunction "1_1") (pintype "passive"))
      (node (ref "MOD2") (pin "OUT1") (pinfunction "OUT1_OUT1") (pintype "output"))
      (node (ref "MOD2") (pin "OUT2") (pinfunction "OUT1_OUT2") (pintype "output"))
      (node (ref "MOD2") (pin "OUT3") (pinfunction "OUT1_OUT3") (pintype "output"))
      (node (ref "MOD2") (pin "OUT4") (pinfunction "OUT1_OUT4") (pintype "output"))
    )
    (net (code "28") (name "Net-(JP39-Pad1)") (class "Default")
      (node (ref "JP39") (pin "1") (pinfunction "1_1") (pintype "passive"))
      (node (ref "JP9") (pin "1") (pinfunction "1_1") (pintype "passive"))
      (node (ref "MOD3") (pin "OUT1") (pinfunction "OUT1_OUT1") (pintype "output"))
      (node (ref "MOD3") (pin "OUT2") (pinfunction "OUT1_OUT2") (pintype "output"))
      (node (ref "MOD3") (pin "OUT3") (pinfunction "OUT1_OUT3") (pintype "output"))
      (node (ref "MOD3") (pin "OUT4") (pinfunction "OUT1_OUT4") (pintype "output"))
    )
    (net (code "29") (name "Net-(JP45-Pad1)") (class "Default")
      (node (ref "JP45") (pin "1") (pinfunction "1_1") (pintype "passive"))
      (node (ref "JP7") (pin "1") (pinfunction "1_1") (pintype "passive"))
      (node (ref "MOD7") (pin "OUT1") (pinfunction "OUT1_OUT1") (pintype "output"))
      (node (ref "MOD7") (pin "OUT2") (pinfunction "OUT1_OUT2") (pintype "output"))
      (node (ref "MOD7") (pin "OUT3") (pinfunction "OUT1_OUT3") (pintype "output"))
      (node (ref "MOD7") (pin "OUT4") (pinfunction "OUT1_OUT4") (pintype "output"))
    )
    (net (code "30") (name "Net-(P1-P$1)") (class "Default")
      (node (ref "JP42") (pin "1") (pinfunction "1_1") (pintype "passive"))
      (node (ref "MOD1") (pin "IN1") (pinfunction "IN1_IN1") (pintype "input"))
      (node (ref "MOD1") (pin "IN2") (pinfunction "IN1_IN2") (pintype "input"))
      (node (ref "MOD1") (pin "IN3") (pinfunction "IN1_IN3") (pintype "input"))
      (node (ref "MOD1") (pin "IN4") (pinfunction "IN1_IN4") (pintype "input"))
      (node (ref "P1") (pin "1") (pinfunction "P$1_1") (pintype "bidirectional"))
    )
    (net (code "31") (name "Net-(P2-P$1)") (class "Default")
      (node (ref "MOD1") (pin "IN2_1") (pinfunction "IN2_IN2_1") (pintype "input"))
      (node (ref "MOD1") (pin "IN2_2") (pinfunction "IN2_IN2_2") (pintype "input"))
      (node (ref "MOD1") (pin "IN2_3") (pinfunction "IN2_IN2_3") (pintype "input"))
      (node (ref "MOD1") (pin "IN2_4") (pinfunction "IN2_IN2_4") (pintype "input"))
      (node (ref "P2") (pin "1") (pinfunction "P$1_1") (pintype "bidirectional"))
    )
    (net (code "32") (name "Net-(P3-P$1)") (class "Default")
      (node (ref "JP43") (pin "1") (pinfunction "1_1") (pintype "passive"))
      (node (ref "MOD6") (pin "IN1") (pinfunction "IN1_IN1") (pintype "input"))
      (node (ref "MOD6") (pin "IN2") (pinfunction "IN1_IN2") (pintype "input"))
      (node (ref "MOD6") (pin "IN3") (pinfunction "IN1_IN3") (pintype "input"))
      (node (ref "MOD6") (pin "IN4") (pinfunction "IN1_IN4") (pintype "input"))
      (node (ref "P3") (pin "1") (pinfunction "P$1_1") (pintype "bidirectional"))
    )
    (net (code "33") (name "Net-(P4-P$1)") (class "Default")
      (node (ref "MOD6") (pin "IN2_1") (pinfunction "IN2_IN2_1") (pintype "input"))
      (node (ref "MOD6") (pin "IN2_2") (pinfunction "IN2_IN2_2") (pintype "input"))
      (node (ref "MOD6") (pin "IN2_3") (pinfunction "IN2_IN2_3") (pintype "input"))
      (node (ref "MOD6") (pin "IN2_4") (pinfunction "IN2_IN2_4") (pintype "input"))
      (node (ref "P4") (pin "1") (pinfunction "P$1_1") (pintype "bidirectional"))
    )
    (net (code "34") (name "Net-(P6-P$1)") (class "Default")
      (node (ref "JP22") (pin "1") (pinfunction "1_1") (pintype "passive"))
      (node (ref "P6") (pin "1") (pinfunction "P$1_1") (pintype "bidirectional"))
    )
    (net (code "35") (name "Net-(P10-P$1)") (class "Default")
      (node (ref "JP41") (pin "1") (pinfunction "1_1") (pintype "passive"))
      (node (ref "MOD5") (pin "OUT1") (pinfunction "OUT1_OUT1") (pintype "output"))
      (node (ref "MOD5") (pin "OUT2") (pinfunction "OUT1_OUT2") (pintype "output"))
      (node (ref "MOD5") (pin "OUT3") (pinfunction "OUT1_OUT3") (pintype "output"))
      (node (ref "MOD5") (pin "OUT4") (pinfunction "OUT1_OUT4") (pintype "output"))
      (node (ref "P10") (pin "1") (pinfunction "P$1_1") (pintype "bidirectional"))
    )
    (net (code "36") (name "Net-(P11-P$1)") (class "Default")
      (node (ref "MOD5") (pin "OUT2_1") (pinfunction "OUT2_OUT2_1") (pintype "output"))
      (node (ref "MOD5") (pin "OUT2_2") (pinfunction "OUT2_OUT2_2") (pintype "output"))
      (node (ref "MOD5") (pin "OUT2_3") (pinfunction "OUT2_OUT2_3") (pintype "output"))
      (node (ref "MOD5") (pin "OUT2_4") (pinfunction "OUT2_OUT2_4") (pintype "output"))
      (node (ref "P11") (pin "1") (pinfunction "P$1_1") (pintype "bidirectional"))
    )
    (net (code "37") (name "Net-(P12-P$1)") (class "Default")
      (node (ref "JP48") (pin "1") (pinfunction "1_1") (pintype "passive"))
      (node (ref "MOD10") (pin "OUT1") (pinfunction "OUT1_OUT1") (pintype "output"))
      (node (ref "MOD10") (pin "OUT2") (pinfunction "OUT1_OUT2") (pintype "output"))
      (node (ref "MOD10") (pin "OUT3") (pinfunction "OUT1_OUT3") (pintype "output"))
      (node (ref "MOD10") (pin "OUT4") (pinfunction "OUT1_OUT4") (pintype "output"))
      (node (ref "P12") (pin "1") (pinfunction "P$1_1") (pintype "bidirectional"))
    )
    (net (code "38") (name "Net-(P13-P$1)") (class "Default")
      (node (ref "MOD10") (pin "OUT2_1") (pinfunction "OUT2_OUT2_1") (pintype "output"))
      (node (ref "MOD10") (pin "OUT2_2") (pinfunction "OUT2_OUT2_2") (pintype "output"))
      (node (ref "MOD10") (pin "OUT2_3") (pinfunction "OUT2_OUT2_3") (pintype "output"))
      (node (ref "MOD10") (pin "OUT2_4") (pinfunction "OUT2_OUT2_4") (pintype "output"))
      (node (ref "P13") (pin "1") (pinfunction "P$1_1") (pintype "bidirectional"))
    )
    (net (code "39") (name "Net-(P19-P$1)") (class "Default")
      (node (ref "JP17") (pin "1") (pinfunction "1_1") (pintype "passive"))
      (node (ref "P19") (pin "1") (pinfunction "P$1_1") (pintype "bidirectional"))
    )
    (net (code "40") (name "Net-(P20-P$1)") (class "Default")
      (node (ref "JP18") (pin "1") (pinfunction "1_1") (pintype "passive"))
      (node (ref "P20") (pin "1") (pinfunction "P$1_1") (pintype "bidirectional"))
    )
    (net (code "41") (name "Net-(P21-P$1)") (class "Default")
      (node (ref "JP19") (pin "1") (pinfunction "1_1") (pintype "passive"))
      (node (ref "P21") (pin "1") (pinfunction "P$1_1") (pintype "bidirectional"))
    )
    (net (code "42") (name "Net-(P22-P$1)") (class "Default")
      (node (ref "JP20") (pin "1") (pinfunction "1_1") (pintype "passive"))
      (node (ref "P22") (pin "1") (pinfunction "P$1_1") (pintype "bidirectional"))
    )
    (net (code "43") (name "Net-(P23-P$1)") (class "Default")
      (node (ref "J2") (pin "5") (pinfunction "5_5") (pintype "passive"))
      (node (ref "JP56") (pin "1") (pinfunction "1_1") (pintype "passive"))
      (node (ref "P23") (pin "1") (pinfunction "P$1_1") (pintype "bidirectional"))
      (node (ref "S2") (pin "11") (pinfunction "P4_11") (pintype "passive"))
    )
    (net (code "44") (name "Net-(P28-P$1)") (class "Default")
      (node (ref "J2") (pin "2") (pinfunction "2_2") (pintype "passive"))
      (node (ref "JP53") (pin "1") (pinfunction "1_1") (pintype "passive"))
      (node (ref "P28") (pin "1") (pinfunction "P$1_1") (pintype "bidirectional"))
      (node (ref "S2") (pin "17") (pinfunction "P6_17") (pintype "passive"))
    )
    (net (code "45") (name "Net-(S2-O2)") (class "Default")
      (node (ref "JP21") (pin "1") (pinfunction "1_1") (pintype "passive"))
      (node (ref "S2") (pin "4") (pinfunction "O2_4") (pintype "passive"))
    )
    (net (code "46") (name "Net-(S2-P2)") (class "Default")
      (node (ref "JP21") (pin "2") (pinfunction "2_2") (pintype "passive"))
      (node (ref "S2") (pin "5") (pinfunction "P2_5") (pintype "passive"))
    )
    (net (code "47") (name "Net-(S2-S2)") (class "Default")
      (node (ref "JP21") (pin "3") (pinfunction "3_3") (pintype "passive"))
      (node (ref "S2") (pin "6") (pinfunction "S2_6") (pintype "passive"))
    )
    (net (code "48") (name "VEH") (class "Default")
      (node (ref "MOD1") (pin "VEH") (pinfunction "VEH_VEH") (pintype "power_in"))
      (node (ref "MOD10") (pin "VEH") (pinfunction "VEH_VEH") (pintype "power_in"))
      (node (ref "MOD2") (pin "VEH") (pinfunction "VEH_VEH") (pintype "power_in"))
      (node (ref "MOD3") (pin "VEH") (pinfunction "VEH_VEH") (pintype "power_in"))
      (node (ref "MOD4") (pin "VEH") (pinfunction "VEH_VEH") (pintype "power_in"))
      (node (ref "MOD5") (pin "VEH") (pinfunction "VEH_VEH") (pintype "power_in"))
      (node (ref "MOD6") (pin "VEH") (pinfunction "VEH_VEH") (pintype "power_in"))
      (node (ref "MOD7") (pin "VEH") (pinfunction "VEH_VEH") (pintype "power_in"))
      (node (ref "MOD8") (pin "VEH") (pinfunction "VEH_VEH") (pintype "power_in"))
      (node (ref "MOD9") (pin "VEH") (pinfunction "VEH_VEH") (pintype "power_in"))
      (node (ref "S2") (pin "16") (pinfunction "S6_16") (pintype "passive"))
    )
    (net (code "49") (name "VSS") (class "Default")
      (node (ref "MOD1") (pin "VSS") (pinfunction "VSS_VSS") (pintype "power_in"))
      (node (ref "MOD10") (pin "VSS") (pinfunction "VSS_VSS") (pintype "power_in"))
      (node (ref "MOD2") (pin "VSS") (pinfunction "VSS_VSS") (pintype "power_in"))
      (node (ref "MOD3") (pin "VSS") (pinfunction "VSS_VSS") (pintype "power_in"))
      (node (ref "MOD4") (pin "VSS") (pinfunction "VSS_VSS") (pintype "power_in"))
      (node (ref "MOD5") (pin "VSS") (pinfunction "VSS_VSS") (pintype "power_in"))
      (node (ref "MOD6") (pin "VSS") (pinfunction "VSS_VSS") (pintype "power_in"))
      (node (ref "MOD7") (pin "VSS") (pinfunction "VSS_VSS") (pintype "power_in"))
      (node (ref "MOD8") (pin "VSS") (pinfunction "VSS_VSS") (pintype "power_in"))
      (node (ref "MOD9") (pin "VSS") (pinfunction "VSS_VSS") (pintype "power_in"))
      (node (ref "S2") (pin "10") (pinfunction "S4_10") (pintype "passive"))
    )
    (net (code "50") (name "unconnected-(S2-O1-Pad1)") (class "Default")
      (node (ref "S2") (pin "1") (pinfunction "O1_1") (pintype "passive"))
    )
    (net (code "51") (name "unconnected-(S2-O3-Pad7)") (class "Default")
      (node (ref "S2") (pin "7") (pinfunction "O3_7") (pintype "passive"))
    )
    (net (code "52") (name "unconnected-(S2-O4-Pad12)") (class "Default")
      (node (ref "S2") (pin "12") (pinfunction "O4_12") (pintype "passive"))
    )
    (net (code "53") (name "unconnected-(S2-O6-Pad18)") (class "Default")
      (node (ref "S2") (pin "18") (pinfunction "O6_18") (pintype "passive"))
    )
    (net (code "54") (name "unconnected-(S2-P5-Pad14)") (class "Default")
      (node (ref "S2") (pin "14") (pinfunction "P5_14") (pintype "passive"))
    )
  )
)
